# CrowPanel_ESP32_Display_1_28_R_Inch_V1_0.net
KiCad netlist of a schematic drawn in EAGLE
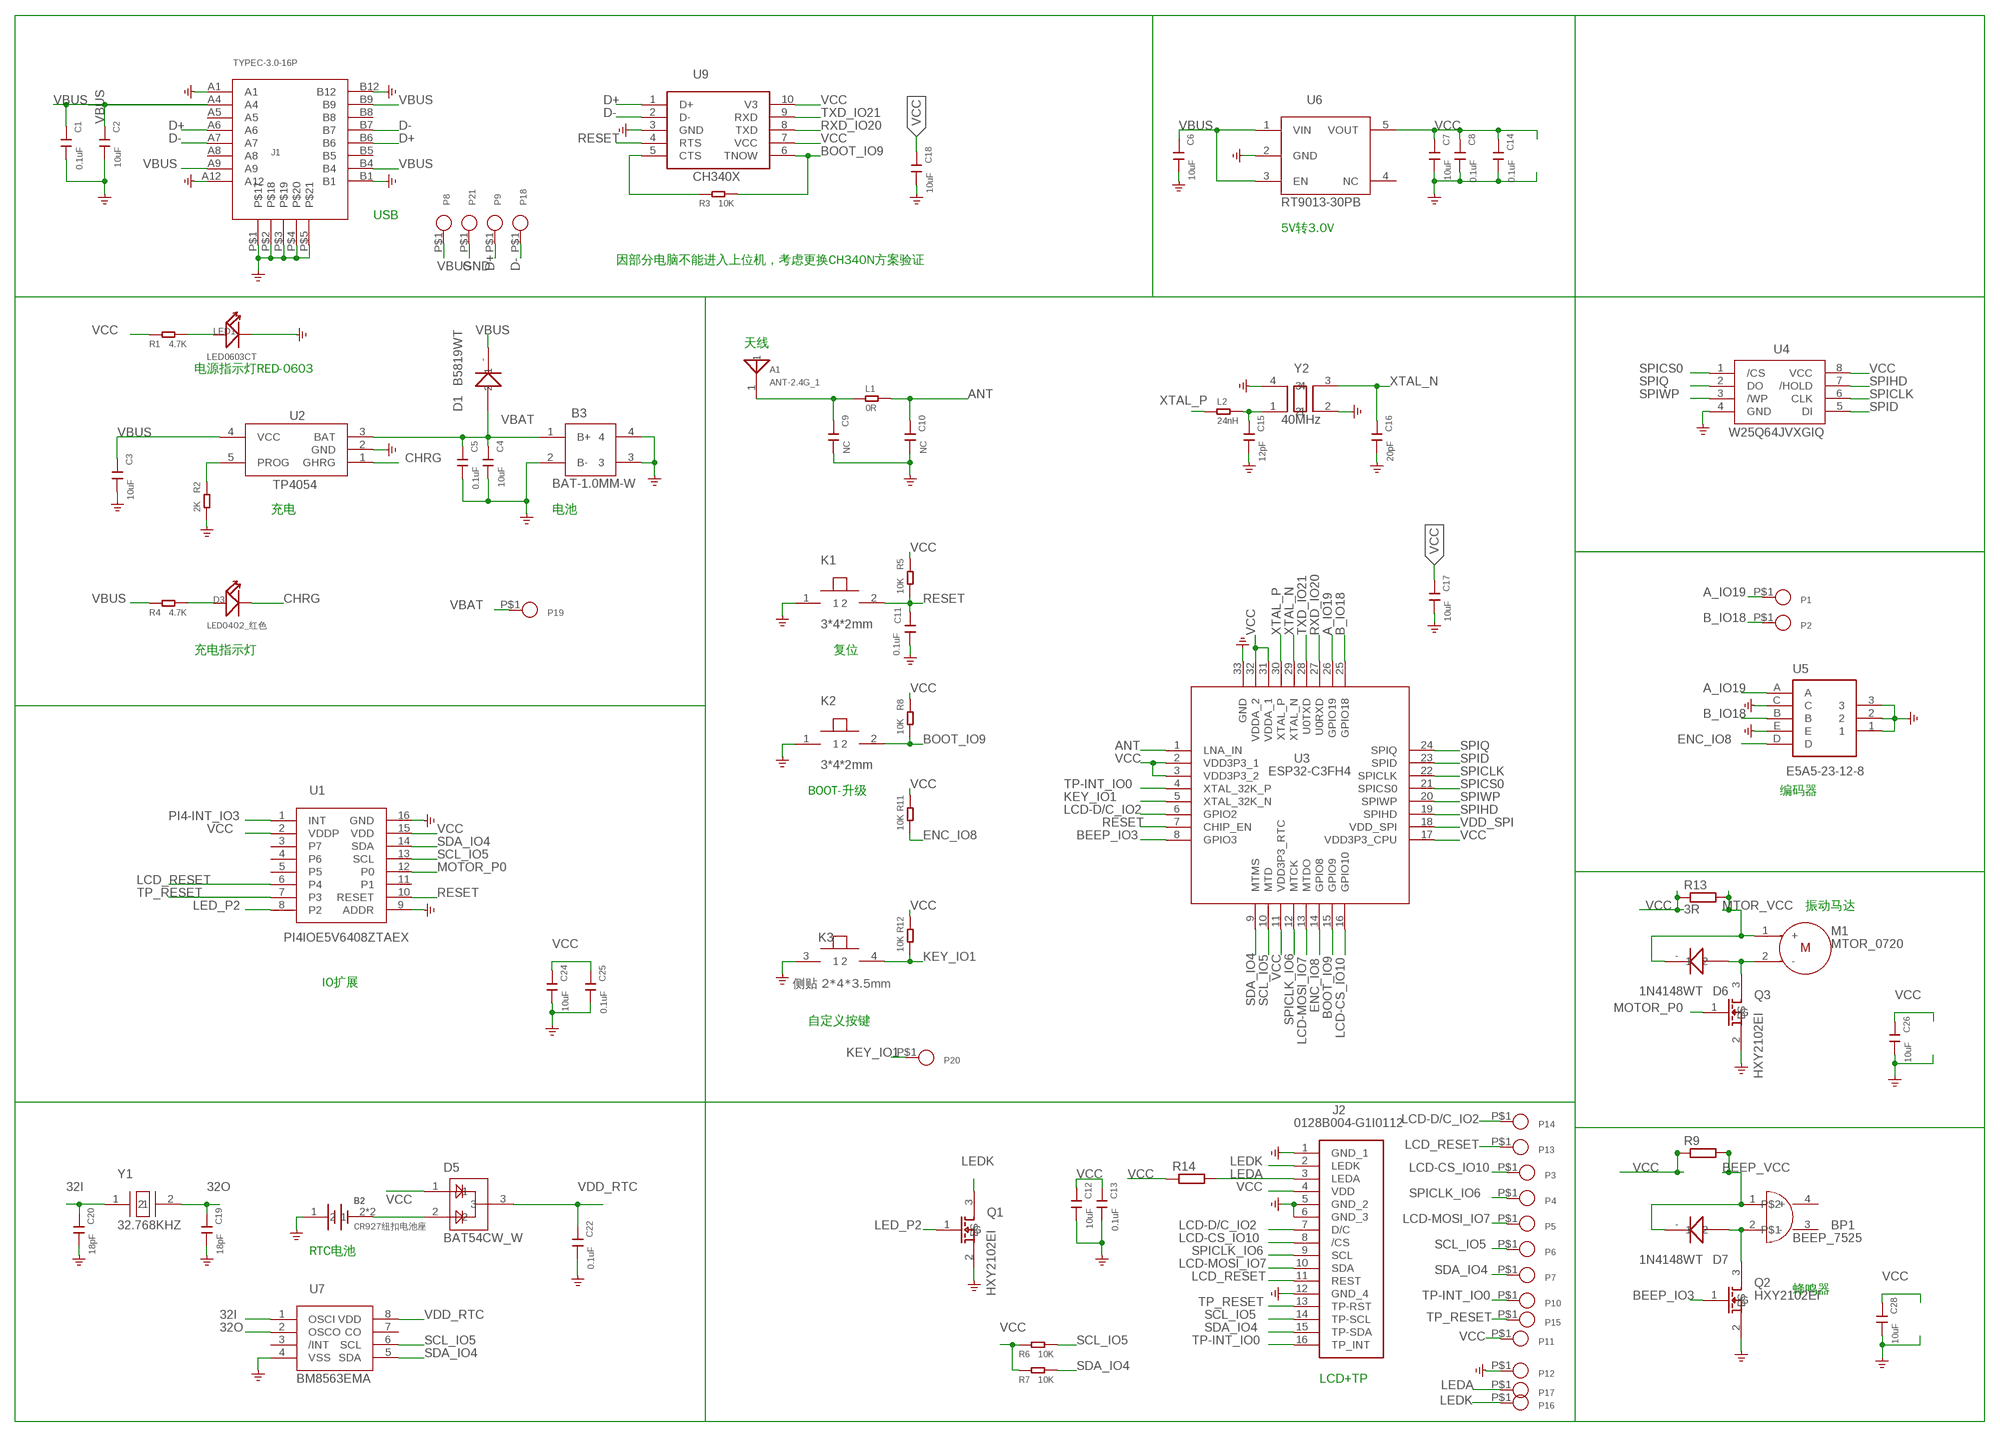
[diagram p0: schematic, sheet 1]

(export (version "E")
  (design (tool "Eeschema 10.0.6"))
  (components
    (comp (ref "A1")
      (value "ANT-2.4G_1")
      (footprint "eagle-import:ANT-2.4G_1")
      (libsource (lib "eagle-import") (part "ANT-2.4G_1"))
    )
    (comp (ref "B2")
      (value "CR927纽扣电池座")
      (footprint "eagle-import:POWER-BAT")
      (libsource (lib "eagle-import") (part "POWER-BAT"))
    )
    (comp (ref "B3")
      (value "BAT-1.0MM-W")
      (footprint "eagle-import:SH1.0MM-W")
      (libsource (lib "eagle-import") (part "BAT-1.0MM-W"))
    )
    (comp (ref "BP1")
      (value "BEEP_7525")
      (footprint "eagle-import:BEEP_7525")
      (libsource (lib "eagle-import") (part "BEEP_7525"))
    )
    (comp (ref "C1")
      (value "0.1uF")
      (footprint "eagle-import:0201_W")
      (libsource (lib "eagle-import") (part "C0402"))
    )
    (comp (ref "C2")
      (value "10uF")
      (footprint "eagle-import:0402")
      (libsource (lib "eagle-import") (part "C0402_W"))
    )
    (comp (ref "C3")
      (value "10uF")
      (footprint "eagle-import:0402")
      (libsource (lib "eagle-import") (part "C0402_W"))
    )
    (comp (ref "C4")
      (value "10uF")
      (footprint "eagle-import:0402")
      (libsource (lib "eagle-import") (part "C0402_W"))
    )
    (comp (ref "C5")
      (value "0.1uF")
      (footprint "eagle-import:0201_W")
      (libsource (lib "eagle-import") (part "C0402"))
    )
    (comp (ref "C6")
      (value "10uF")
      (footprint "eagle-import:0402")
      (libsource (lib "eagle-import") (part "C0402_W"))
    )
    (comp (ref "C7")
      (value "10uF")
      (footprint "eagle-import:0402")
      (libsource (lib "eagle-import") (part "C0402_W"))
    )
    (comp (ref "C8")
      (value "0.1uF")
      (footprint "eagle-import:0201_W")
      (libsource (lib "eagle-import") (part "C0402"))
    )
    (comp (ref "C9")
      (value "NC")
      (footprint "eagle-import:0201_W")
      (libsource (lib "eagle-import") (part "C0402"))
    )
    (comp (ref "C10")
      (value "NC")
      (footprint "eagle-import:0201_W")
      (libsource (lib "eagle-import") (part "C0402"))
    )
    (comp (ref "C11")
      (value "0.1uF")
      (footprint "eagle-import:0201_W")
      (libsource (lib "eagle-import") (part "C0402"))
    )
    (comp (ref "C12")
      (value "10uF")
      (footprint "eagle-import:0402")
      (libsource (lib "eagle-import") (part "C0402_W"))
    )
    (comp (ref "C13")
      (value "0.1uF")
      (footprint "eagle-import:0201_W")
      (libsource (lib "eagle-import") (part "C0402"))
    )
    (comp (ref "C14")
      (value "0.1uF")
      (footprint "eagle-import:0201_W")
      (libsource (lib "eagle-import") (part "C0402"))
    )
    (comp (ref "C15")
      (value "12pF")
      (footprint "eagle-import:0201_W")
      (libsource (lib "eagle-import") (part "C0402"))
    )
    (comp (ref "C16")
      (value "20pF")
      (footprint "eagle-import:0201_W")
      (libsource (lib "eagle-import") (part "C0402"))
    )
    (comp (ref "C17")
      (value "10uF")
      (footprint "eagle-import:0402")
      (libsource (lib "eagle-import") (part "C0402_W"))
    )
    (comp (ref "C18")
      (value "10uF")
      (footprint "eagle-import:0402")
      (libsource (lib "eagle-import") (part "C0402_W"))
    )
    (comp (ref "C19")
      (value "18pF")
      (footprint "eagle-import:0201_W")
      (libsource (lib "eagle-import") (part "C0402"))
    )
    (comp (ref "C20")
      (value "18pF")
      (footprint "eagle-import:0201_W")
      (libsource (lib "eagle-import") (part "C0402"))
    )
    (comp (ref "C22")
      (value "0.1uF")
      (footprint "eagle-import:0201_W")
      (libsource (lib "eagle-import") (part "C0402"))
    )
    (comp (ref "C24")
      (value "10uF")
      (footprint "eagle-import:0402")
      (libsource (lib "eagle-import") (part "C0402_W"))
    )
    (comp (ref "C25")
      (value "0.1uF")
      (footprint "eagle-import:0201_W")
      (libsource (lib "eagle-import") (part "C0402"))
    )
    (comp (ref "C26")
      (value "10uF")
      (footprint "eagle-import:0402")
      (libsource (lib "eagle-import") (part "C0402_W"))
    )
    (comp (ref "C28")
      (value "10uF")
      (footprint "eagle-import:0402")
      (libsource (lib "eagle-import") (part "C0402_W"))
    )
    (comp (ref "D1")
      (value "B5819WT")
      (footprint "eagle-import:SOD-523")
      (libsource (lib "eagle-import") (part "DIODE_W"))
    )
    (comp (ref "D3")
      (value "LED0402_红色")
      (footprint "eagle-import:LED-0402_W")
      (libsource (lib "eagle-import") (part "LED0402_W"))
    )
    (comp (ref "D5")
      (value "BAT54CW_W")
      (footprint "eagle-import:SOT-323_W")
      (libsource (lib "eagle-import") (part "BAT54CW_W"))
    )
    (comp (ref "D6")
      (value "1N4148WT")
      (footprint "eagle-import:SOD-523")
      (libsource (lib "eagle-import") (part "DIODE_W"))
    )
    (comp (ref "D7")
      (value "1N4148WT")
      (footprint "eagle-import:SOD-523")
      (libsource (lib "eagle-import") (part "DIODE_W"))
    )
    (comp (ref "J1")
      (value "TYPEC-3.0-16P")
      (footprint "eagle-import:KEVIN_3.0TYPEC-SMD")
      (libsource (lib "eagle-import") (part "KEVIN_TYPEC-3.0-16P-SMD"))
    )
    (comp (ref "J2")
      (value "0128B004-G1I0112")
      (footprint "eagle-import:16PIN-SMD")
      (libsource (lib "eagle-import") (part "0128B004-G1I0112"))
    )
    (comp (ref "K1")
      (value "3*4*2mm")
      (footprint "eagle-import:KEY-3X4_W")
      (libsource (lib "eagle-import") (part "KEY_3X4_W"))
    )
    (comp (ref "K2")
      (value "3*4*2mm")
      (footprint "eagle-import:KEY-3X4_W")
      (libsource (lib "eagle-import") (part "KEY_3X4_W"))
    )
    (comp (ref "K3")
      (value "侧贴 2*4*3.5mm")
      (footprint "eagle-import:KEY-3.5X4.5_C")
      (libsource (lib "eagle-import") (part "KEY_2X4X3.5_W"))
    )
    (comp (ref "L1")
      (value "0R")
      (footprint "eagle-import:0201_W")
      (libsource (lib "eagle-import") (part "R0402"))
    )
    (comp (ref "L2")
      (value "24nH")
      (footprint "eagle-import:0201_W")
      (libsource (lib "eagle-import") (part "R0402"))
    )
    (comp (ref "LED1")
      (value "LED0603CT")
      (footprint "eagle-import:LED-0603-CE")
      (libsource (lib "eagle-import") (part "LED0603CT"))
    )
    (comp (ref "M1")
      (value "MTOR_0720")
      (footprint "eagle-import:MOTOR-1")
      (libsource (lib "eagle-import") (part "MTOR_0720"))
    )
    (comp (ref "P1")
      (value "PADPAD-1.0MM")
      (footprint "eagle-import:PAD-1.0MM")
      (libsource (lib "eagle-import") (part "PADPAD-1.0MM"))
    )
    (comp (ref "P2")
      (value "PADPAD-1.0MM")
      (footprint "eagle-import:PAD-1.0MM")
      (libsource (lib "eagle-import") (part "PADPAD-1.0MM"))
    )
    (comp (ref "P3")
      (value "PADPAD-1.0MM")
      (footprint "eagle-import:PAD-1.0MM")
      (libsource (lib "eagle-import") (part "PADPAD-1.0MM"))
    )
    (comp (ref "P4")
      (value "PADPAD-1.0MM")
      (footprint "eagle-import:PAD-1.0MM")
      (libsource (lib "eagle-import") (part "PADPAD-1.0MM"))
    )
    (comp (ref "P5")
      (value "PADPAD-1.0MM")
      (footprint "eagle-import:PAD-1.0MM")
      (libsource (lib "eagle-import") (part "PADPAD-1.0MM"))
    )
    (comp (ref "P6")
      (value "PADPAD-1.0MM")
      (footprint "eagle-import:PAD-1.0MM")
      (libsource (lib "eagle-import") (part "PADPAD-1.0MM"))
    )
    (comp (ref "P7")
      (value "PADPAD-1.0MM")
      (footprint "eagle-import:PAD-1.0MM")
      (libsource (lib "eagle-import") (part "PADPAD-1.0MM"))
    )
    (comp (ref "P8")
      (value "PADPAD-1.0MM")
      (footprint "eagle-import:PAD-1.0MM")
      (libsource (lib "eagle-import") (part "PADPAD-1.0MM"))
    )
    (comp (ref "P9")
      (value "PADPAD-1.0MM")
      (footprint "eagle-import:PAD-1.0MM")
      (libsource (lib "eagle-import") (part "PADPAD-1.0MM"))
    )
    (comp (ref "P10")
      (value "PADPAD-1.0MM")
      (footprint "eagle-import:PAD-1.0MM")
      (libsource (lib "eagle-import") (part "PADPAD-1.0MM"))
    )
    (comp (ref "P11")
      (value "PADPAD-1.0MM")
      (footprint "eagle-import:PAD-1.0MM")
      (libsource (lib "eagle-import") (part "PADPAD-1.0MM"))
    )
    (comp (ref "P12")
      (value "PADPAD-1.0MM")
      (footprint "eagle-import:PAD-1.0MM")
      (libsource (lib "eagle-import") (part "PADPAD-1.0MM"))
    )
    (comp (ref "P13")
      (value "PADPAD-1.0MM")
      (footprint "eagle-import:PAD-1.0MM")
      (libsource (lib "eagle-import") (part "PADPAD-1.0MM"))
    )
    (comp (ref "P14")
      (value "PADPAD-1.0MM")
      (footprint "eagle-import:PAD-1.0MM")
      (libsource (lib "eagle-import") (part "PADPAD-1.0MM"))
    )
    (comp (ref "P15")
      (value "PADPAD-1.0MM")
      (footprint "eagle-import:PAD-1.0MM")
      (libsource (lib "eagle-import") (part "PADPAD-1.0MM"))
    )
    (comp (ref "P16")
      (value "PADPAD-1.0MM")
      (footprint "eagle-import:PAD-1.0MM")
      (libsource (lib "eagle-import") (part "PADPAD-1.0MM"))
    )
    (comp (ref "P17")
      (value "PADPAD-1.0MM")
      (footprint "eagle-import:PAD-1.0MM")
      (libsource (lib "eagle-import") (part "PADPAD-1.0MM"))
    )
    (comp (ref "P18")
      (value "PADPAD-1.0MM")
      (footprint "eagle-import:PAD-1.0MM")
      (libsource (lib "eagle-import") (part "PADPAD-1.0MM"))
    )
    (comp (ref "P19")
      (value "PADPAD-1.0MM")
      (footprint "eagle-import:PAD-1.0MM")
      (libsource (lib "eagle-import") (part "PADPAD-1.0MM"))
    )
    (comp (ref "P20")
      (value "PADPAD-1.0MM")
      (footprint "eagle-import:PAD-1.0MM")
      (libsource (lib "eagle-import") (part "PADPAD-1.0MM"))
    )
    (comp (ref "P21")
      (value "PADPAD-1.0MM")
      (footprint "eagle-import:PAD-1.0MM")
      (libsource (lib "eagle-import") (part "PADPAD-1.0MM"))
    )
    (comp (ref "Q1")
      (value "HXY2102EI")
      (footprint "eagle-import:SOT-323_W")
      (libsource (lib "eagle-import") (part "HXY2102EI"))
    )
    (comp (ref "Q2")
      (value "HXY2102EI")
      (footprint "eagle-import:SOT-323_W")
      (libsource (lib "eagle-import") (part "HXY2102EI"))
    )
    (comp (ref "Q3")
      (value "HXY2102EI")
      (footprint "eagle-import:SOT-323_W")
      (libsource (lib "eagle-import") (part "HXY2102EI"))
    )
    (comp (ref "R1")
      (value "4.7K")
      (footprint "eagle-import:0201_W")
      (libsource (lib "eagle-import") (part "R0402"))
    )
    (comp (ref "R2")
      (value "2K")
      (footprint "eagle-import:0201_W")
      (libsource (lib "eagle-import") (part "R0402"))
    )
    (comp (ref "R3")
      (value "10K")
      (footprint "eagle-import:0201_W")
      (libsource (lib "eagle-import") (part "R0402"))
    )
    (comp (ref "R4")
      (value "4.7K")
      (footprint "eagle-import:0201_W")
      (libsource (lib "eagle-import") (part "R0402"))
    )
    (comp (ref "R5")
      (value "10K")
      (footprint "eagle-import:0201_W")
      (libsource (lib "eagle-import") (part "R0402"))
    )
    (comp (ref "R6")
      (value "10K")
      (footprint "eagle-import:0201_W")
      (libsource (lib "eagle-import") (part "R0402"))
    )
    (comp (ref "R7")
      (value "10K")
      (footprint "eagle-import:0201_W")
      (libsource (lib "eagle-import") (part "R0402"))
    )
    (comp (ref "R8")
      (value "10K")
      (footprint "eagle-import:0201_W")
      (libsource (lib "eagle-import") (part "R0402"))
    )
    (comp (ref "R9")
      (value "R-EU_R0402")
      (footprint "eagle-import:R0402")
      (libsource (lib "eagle-import") (part "R-EU_R0402"))
    )
    (comp (ref "R11")
      (value "10K")
      (footprint "eagle-import:0201_W")
      (libsource (lib "eagle-import") (part "R0402"))
    )
    (comp (ref "R12")
      (value "10K")
      (footprint "eagle-import:0201_W")
      (libsource (lib "eagle-import") (part "R0402"))
    )
    (comp (ref "R13")
      (value "3R")
      (footprint "eagle-import:R0402")
      (libsource (lib "eagle-import") (part "R-EU_R0402"))
    )
    (comp (ref "R14")
      (value "R-EU_R0402")
      (footprint "eagle-import:R0402")
      (libsource (lib "eagle-import") (part "R-EU_R0402"))
    )
    (comp (ref "U1")
      (value "PI4IOE5V6408ZTAEX")
      (footprint "eagle-import:UQFN-16")
      (libsource (lib "eagle-import") (part "PI4IOE5V6408ZTAEX"))
    )
    (comp (ref "U2")
      (value "TP4054")
      (footprint "eagle-import:SOP23-5")
      (libsource (lib "eagle-import") (part "4054A"))
    )
    (comp (ref "U3")
      (value "ESP32-C3FH4")
      (footprint "eagle-import:QFN-32_W")
      (libsource (lib "eagle-import") (part "ESP32-C3"))
    )
    (comp (ref "U4")
      (value "W25Q64JVXGIQ")
      (footprint "eagle-import:XSON4X4")
      (libsource (lib "eagle-import") (part "W25Q64JVXGIQ"))
    )
    (comp (ref "U5")
      (value "E5A5-23-12-8")
      (footprint "eagle-import:E5A5-23-12-8")
      (fields (field (name "SPICEPREFIX") "X"))
      (libsource (lib "eagle-import") (part "E5A5-23-12-8"))
    )
    (comp (ref "U6")
      (value "RT9013-30PB")
      (footprint "eagle-import:SOT23-5_W")
      (libsource (lib "eagle-import") (part "RT9013"))
    )
    (comp (ref "U7")
      (value "BM8563EMA")
      (footprint "eagle-import:MSOP-8_W")
      (libsource (lib "eagle-import") (part "BM8563EMA"))
    )
    (comp (ref "U9")
      (value "CH340X")
      (footprint "eagle-import:MSOP-10_W")
      (libsource (lib "eagle-import") (part "CH340E"))
    )
    (comp (ref "Y1")
      (value "32.768KHZ")
      (footprint "eagle-import:3215_W")
      (libsource (lib "eagle-import") (part "32.768KHZ"))
    )
    (comp (ref "Y2")
      (value "40MHz")
      (footprint "eagle-import:3225_W")
      (libsource (lib "eagle-import") (part "3225_W"))
    )
  )
  (nets
    (net (code "1") (name "/32I") (class "Default")
      (node (ref "C20") (pin "1") (pinfunction "1_1") (pintype "passive"))
      (node (ref "U7") (pin "1") (pinfunction "OSCI_1") (pintype "bidirectional"))
      (node (ref "Y1") (pin "1") (pinfunction "1_1") (pintype "bidirectional"))
    )
    (net (code "2") (name "/32O") (class "Default")
      (node (ref "C19") (pin "1") (pinfunction "1_1") (pintype "passive"))
      (node (ref "U7") (pin "2") (pinfunction "OSCO_2") (pintype "bidirectional"))
      (node (ref "Y1") (pin "2") (pinfunction "2_2") (pintype "bidirectional"))
    )
    (net (code "3") (name "/ANT") (class "Default")
      (node (ref "C10") (pin "1") (pinfunction "1_1") (pintype "passive"))
      (node (ref "L1") (pin "2") (pinfunction "2_2") (pintype "passive"))
      (node (ref "U3") (pin "1") (pinfunction "LNA_IN_1") (pintype "bidirectional"))
    )
    (net (code "4") (name "/A_IO19") (class "Default")
      (node (ref "P1") (pin "P$1") (pinfunction "P$1_P$1") (pintype "bidirectional"))
      (node (ref "U3") (pin "26") (pinfunction "GPIO19_26") (pintype "bidirectional"))
      (node (ref "U5") (pin "A") (pinfunction "A_A") (pintype "bidirectional"))
    )
    (net (code "5") (name "/BEEP_IO3") (class "Default")
      (node (ref "Q2") (pin "1") (pinfunction "G_1") (pintype "bidirectional"))
      (node (ref "U3") (pin "8") (pinfunction "GPIO3_8") (pintype "bidirectional"))
    )
    (net (code "6") (name "/BEEP_VCC") (class "Default")
      (node (ref "BP1") (pin "1") (pinfunction "+_1") (pintype "bidirectional"))
      (node (ref "D7") (pin "-") (pinfunction "2_-") (pintype "bidirectional"))
      (node (ref "R9") (pin "2") (pinfunction "2_2") (pintype "passive"))
    )
    (net (code "7") (name "/BOOT_IO9") (class "Default")
      (node (ref "K2") (pin "2") (pinfunction "2_2") (pintype "bidirectional"))
      (node (ref "R3") (pin "2") (pinfunction "2_2") (pintype "passive"))
      (node (ref "R8") (pin "2") (pinfunction "2_2") (pintype "passive"))
      (node (ref "U3") (pin "15") (pinfunction "GPIO9_15") (pintype "bidirectional"))
      (node (ref "U9") (pin "6") (pinfunction "TNOW_6") (pintype "bidirectional"))
    )
    (net (code "8") (name "/B_IO18") (class "Default")
      (node (ref "P2") (pin "P$1") (pinfunction "P$1_P$1") (pintype "bidirectional"))
      (node (ref "U3") (pin "25") (pinfunction "GPIO18_25") (pintype "bidirectional"))
      (node (ref "U5") (pin "B") (pinfunction "B_B") (pintype "bidirectional"))
    )
    (net (code "9") (name "/CHRG") (class "Default")
      (node (ref "D3") (pin "2") (pinfunction "-_2") (pintype "passive"))
      (node (ref "U2") (pin "1") (pinfunction "GHRG_1") (pintype "bidirectional"))
    )
    (net (code "10") (name "/D+") (class "Default")
      (node (ref "J1") (pin "A6") (pinfunction "A6_A6") (pintype "bidirectional"))
      (node (ref "J1") (pin "B6") (pinfunction "B6_B6") (pintype "bidirectional"))
      (node (ref "P9") (pin "P$1") (pinfunction "P$1_P$1") (pintype "bidirectional"))
      (node (ref "U9") (pin "1") (pinfunction "D+_1") (pintype "bidirectional"))
    )
    (net (code "11") (name "/D-") (class "Default")
      (node (ref "J1") (pin "A7") (pinfunction "A7_A7") (pintype "bidirectional"))
      (node (ref "J1") (pin "B7") (pinfunction "B7_B7") (pintype "bidirectional"))
      (node (ref "P18") (pin "P$1") (pinfunction "P$1_P$1") (pintype "bidirectional"))
      (node (ref "U9") (pin "2") (pinfunction "D-_2") (pintype "bidirectional"))
    )
    (net (code "12") (name "/ENC_IO8") (class "Default")
      (node (ref "R11") (pin "2") (pinfunction "2_2") (pintype "passive"))
      (node (ref "U3") (pin "14") (pinfunction "GPIO8_14") (pintype "bidirectional"))
      (node (ref "U5") (pin "D") (pinfunction "D_D") (pintype "bidirectional"))
    )
    (net (code "13") (name "/KEY_IO1") (class "Default")
      (node (ref "K3") (pin "4") (pinfunction "2_4") (pintype "bidirectional"))
      (node (ref "P20") (pin "P$1") (pinfunction "P$1_P$1") (pintype "bidirectional"))
      (node (ref "R12") (pin "2") (pinfunction "2_2") (pintype "passive"))
      (node (ref "U3") (pin "5") (pinfunction "XTAL_32K_N_5") (pintype "bidirectional"))
    )
    (net (code "14") (name "/LCD-CS_IO10") (class "Default")
      (node (ref "J2") (pin "8") (pinfunction "/CS_8") (pintype "bidirectional"))
      (node (ref "P3") (pin "P$1") (pinfunction "P$1_P$1") (pintype "bidirectional"))
      (node (ref "U3") (pin "16") (pinfunction "GPIO10_16") (pintype "bidirectional"))
    )
    (net (code "15") (name "/LCD-D{slash}C_IO2") (class "Default")
      (node (ref "J2") (pin "7") (pinfunction "D/C_7") (pintype "bidirectional"))
      (node (ref "P14") (pin "P$1") (pinfunction "P$1_P$1") (pintype "bidirectional"))
      (node (ref "U3") (pin "6") (pinfunction "GPIO2_6") (pintype "bidirectional"))
    )
    (net (code "16") (name "/LCD-MOSI_IO7") (class "Default")
      (node (ref "J2") (pin "10") (pinfunction "SDA_10") (pintype "bidirectional"))
      (node (ref "P5") (pin "P$1") (pinfunction "P$1_P$1") (pintype "bidirectional"))
      (node (ref "U3") (pin "13") (pinfunction "MTDO_13") (pintype "bidirectional"))
    )
    (net (code "17") (name "/LCD_RESET") (class "Default")
      (node (ref "J2") (pin "11") (pinfunction "REST_11") (pintype "bidirectional"))
      (node (ref "P13") (pin "P$1") (pinfunction "P$1_P$1") (pintype "bidirectional"))
      (node (ref "U1") (pin "6") (pinfunction "P4_6") (pintype "bidirectional"))
    )
    (net (code "18") (name "/LEDA") (class "Default")
      (node (ref "J2") (pin "3") (pinfunction "LEDA_3") (pintype "bidirectional"))
      (node (ref "P17") (pin "P$1") (pinfunction "P$1_P$1") (pintype "bidirectional"))
      (node (ref "R14") (pin "2") (pinfunction "2_2") (pintype "passive"))
    )
    (net (code "19") (name "/LEDK") (class "Default")
      (node (ref "J2") (pin "2") (pinfunction "LEDK_2") (pintype "bidirectional"))
      (node (ref "P16") (pin "P$1") (pinfunction "P$1_P$1") (pintype "bidirectional"))
      (node (ref "Q1") (pin "3") (pinfunction "D_3") (pintype "bidirectional"))
    )
    (net (code "20") (name "/LED_P2") (class "Default")
      (node (ref "Q1") (pin "1") (pinfunction "G_1") (pintype "bidirectional"))
      (node (ref "U1") (pin "8") (pinfunction "P2_8") (pintype "bidirectional"))
    )
    (net (code "21") (name "/MOTOR_P0") (class "Default")
      (node (ref "Q3") (pin "1") (pinfunction "G_1") (pintype "bidirectional"))
      (node (ref "U1") (pin "12") (pinfunction "P0_12") (pintype "bidirectional"))
    )
    (net (code "22") (name "/MTOR_VCC") (class "Default")
      (node (ref "D6") (pin "-") (pinfunction "2_-") (pintype "bidirectional"))
      (node (ref "M1") (pin "1") (pinfunction "+_1") (pintype "bidirectional"))
      (node (ref "R13") (pin "2") (pinfunction "2_2") (pintype "passive"))
    )
    (net (code "23") (name "/PI4-INT_IO3") (class "Default")
      (node (ref "U1") (pin "1") (pinfunction "INT_1") (pintype "bidirectional"))
    )
    (net (code "24") (name "/RESET") (class "Default")
      (node (ref "C11") (pin "1") (pinfunction "1_1") (pintype "passive"))
      (node (ref "K1") (pin "2") (pinfunction "2_2") (pintype "bidirectional"))
      (node (ref "R5") (pin "2") (pinfunction "2_2") (pintype "passive"))
      (node (ref "U1") (pin "10") (pinfunction "RESET_10") (pintype "bidirectional"))
      (node (ref "U3") (pin "7") (pinfunction "CHIP_EN_7") (pintype "bidirectional"))
      (node (ref "U9") (pin "4") (pinfunction "RTS_4") (pintype "bidirectional"))
    )
    (net (code "25") (name "/RXD_IO20") (class "Default")
      (node (ref "U3") (pin "27") (pinfunction "U0RXD_27") (pintype "bidirectional"))
      (node (ref "U9") (pin "8") (pinfunction "TXD_8") (pintype "bidirectional"))
    )
    (net (code "26") (name "/SCL_IO5") (class "Default")
      (node (ref "J2") (pin "14") (pinfunction "TP-SCL_14") (pintype "bidirectional"))
      (node (ref "P6") (pin "P$1") (pinfunction "P$1_P$1") (pintype "bidirectional"))
      (node (ref "R6") (pin "2") (pinfunction "2_2") (pintype "passive"))
      (node (ref "U1") (pin "13") (pinfunction "SCL_13") (pintype "bidirectional"))
      (node (ref "U3") (pin "10") (pinfunction "MTD_10") (pintype "bidirectional"))
      (node (ref "U7") (pin "6") (pinfunction "SCL_6") (pintype "bidirectional"))
    )
    (net (code "27") (name "/SDA_IO4") (class "Default")
      (node (ref "J2") (pin "15") (pinfunction "TP-SDA_15") (pintype "bidirectional"))
      (node (ref "P7") (pin "P$1") (pinfunction "P$1_P$1") (pintype "bidirectional"))
      (node (ref "R7") (pin "2") (pinfunction "2_2") (pintype "passive"))
      (node (ref "U1") (pin "14") (pinfunction "SDA_14") (pintype "bidirectional"))
      (node (ref "U3") (pin "9") (pinfunction "MTMS_9") (pintype "bidirectional"))
      (node (ref "U7") (pin "5") (pinfunction "SDA_5") (pintype "bidirectional"))
    )
    (net (code "28") (name "/SPICLK") (class "Default")
      (node (ref "U3") (pin "22") (pinfunction "SPICLK_22") (pintype "bidirectional"))
      (node (ref "U4") (pin "6") (pinfunction "CLK_6") (pintype "bidirectional"))
    )
    (net (code "29") (name "/SPICLK_IO6") (class "Default")
      (node (ref "J2") (pin "9") (pinfunction "SCL_9") (pintype "bidirectional"))
      (node (ref "P4") (pin "P$1") (pinfunction "P$1_P$1") (pintype "bidirectional"))
      (node (ref "U3") (pin "12") (pinfunction "MTCK_12") (pintype "bidirectional"))
    )
    (net (code "30") (name "/SPICS0") (class "Default")
      (node (ref "U3") (pin "21") (pinfunction "SPICS0_21") (pintype "bidirectional"))
      (node (ref "U4") (pin "1") (pinfunction "/CS_1") (pintype "bidirectional"))
    )
    (net (code "31") (name "/SPID") (class "Default")
      (node (ref "U3") (pin "23") (pinfunction "SPID_23") (pintype "bidirectional"))
      (node (ref "U4") (pin "5") (pinfunction "DI_5") (pintype "bidirectional"))
    )
    (net (code "32") (name "/SPIHD") (class "Default")
      (node (ref "U3") (pin "19") (pinfunction "SPIHD_19") (pintype "bidirectional"))
      (node (ref "U4") (pin "7") (pinfunction "/HOLD_7") (pintype "bidirectional"))
    )
    (net (code "33") (name "/SPIQ") (class "Default")
      (node (ref "U3") (pin "24") (pinfunction "SPIQ_24") (pintype "bidirectional"))
      (node (ref "U4") (pin "2") (pinfunction "DO_2") (pintype "bidirectional"))
    )
    (net (code "34") (name "/SPIWP") (class "Default")
      (node (ref "U3") (pin "20") (pinfunction "SPIWP_20") (pintype "bidirectional"))
      (node (ref "U4") (pin "3") (pinfunction "/WP_3") (pintype "bidirectional"))
    )
    (net (code "35") (name "/TP-INT_IO0") (class "Default")
      (node (ref "J2") (pin "16") (pinfunction "TP_INT_16") (pintype "bidirectional"))
      (node (ref "P10") (pin "P$1") (pinfunction "P$1_P$1") (pintype "bidirectional"))
      (node (ref "U3") (pin "4") (pinfunction "XTAL_32K_P_4") (pintype "bidirectional"))
    )
    (net (code "36") (name "/TP_RESET") (class "Default")
      (node (ref "J2") (pin "13") (pinfunction "TP-RST_13") (pintype "bidirectional"))
      (node (ref "P15") (pin "P$1") (pinfunction "P$1_P$1") (pintype "bidirectional"))
      (node (ref "U1") (pin "7") (pinfunction "P3_7") (pintype "bidirectional"))
    )
    (net (code "37") (name "/TXD_IO21") (class "Default")
      (node (ref "U3") (pin "28") (pinfunction "U0TXD_28") (pintype "bidirectional"))
      (node (ref "U9") (pin "9") (pinfunction "RXD_9") (pintype "bidirectional"))
    )
    (net (code "38") (name "/VBAT") (class "Default")
      (node (ref "B3") (pin "1") (pinfunction "B+_1") (pintype "bidirectional"))
      (node (ref "C4") (pin "1") (pinfunction "1_1") (pintype "passive"))
      (node (ref "C5") (pin "1") (pinfunction "1_1") (pintype "passive"))
      (node (ref "D1") (pin "+") (pinfunction "1_+") (pintype "bidirectional"))
      (node (ref "P19") (pin "P$1") (pinfunction "P$1_P$1") (pintype "bidirectional"))
      (node (ref "U2") (pin "3") (pinfunction "BAT_3") (pintype "bidirectional"))
    )
    (net (code "39") (name "/VBUS") (class "Default")
      (node (ref "C1") (pin "1") (pinfunction "1_1") (pintype "passive"))
      (node (ref "C2") (pin "1") (pinfunction "1_1") (pintype "passive"))
      (node (ref "C3") (pin "1") (pinfunction "1_1") (pintype "passive"))
      (node (ref "C6") (pin "1") (pinfunction "1_1") (pintype "passive"))
      (node (ref "D1") (pin "-") (pinfunction "2_-") (pintype "bidirectional"))
      (node (ref "J1") (pin "A4") (pinfunction "A4_A4") (pintype "bidirectional"))
      (node (ref "J1") (pin "A9") (pinfunction "A9_A9") (pintype "bidirectional"))
      (node (ref "J1") (pin "B4") (pinfunction "B4_B4") (pintype "bidirectional"))
      (node (ref "J1") (pin "B9") (pinfunction "B9_B9") (pintype "bidirectional"))
      (node (ref "P8") (pin "P$1") (pinfunction "P$1_P$1") (pintype "bidirectional"))
      (node (ref "R4") (pin "1") (pinfunction "1_1") (pintype "passive"))
      (node (ref "U2") (pin "4") (pinfunction "VCC_4") (pintype "bidirectional"))
      (node (ref "U6") (pin "1") (pinfunction "VIN_1") (pintype "bidirectional"))
      (node (ref "U6") (pin "3") (pinfunction "EN_3") (pintype "bidirectional"))
    )
    (net (code "40") (name "/VDD_RTC") (class "Default")
      (node (ref "C22") (pin "1") (pinfunction "1_1") (pintype "passive"))
      (node (ref "D5") (pin "3") (pinfunction "3_3") (pintype "bidirectional"))
      (node (ref "U7") (pin "8") (pinfunction "VDD_8") (pintype "bidirectional"))
    )
    (net (code "41") (name "/VDD_SPI") (class "Default")
      (node (ref "U3") (pin "18") (pinfunction "VDD_SPI_18") (pintype "bidirectional"))
    )
    (net (code "42") (name "/XTAL_N") (class "Default")
      (node (ref "C16") (pin "1") (pinfunction "1_1") (pintype "passive"))
      (node (ref "U3") (pin "29") (pinfunction "XTAL_N_29") (pintype "bidirectional"))
      (node (ref "Y2") (pin "3") (pinfunction "3_3") (pintype "bidirectional"))
    )
    (net (code "43") (name "/XTAL_P") (class "Default")
      (node (ref "L2") (pin "1") (pinfunction "1_1") (pintype "passive"))
      (node (ref "U3") (pin "30") (pinfunction "XTAL_P_30") (pintype "bidirectional"))
    )
    (net (code "44") (name "GND_W") (class "Default")
      (node (ref "B2") (pin "1") (pinfunction "1_1") (pintype "bidirectional"))
      (node (ref "B3") (pin "2") (pinfunction "B-_2") (pintype "bidirectional"))
      (node (ref "B3") (pin "3") (pinfunction "3_3") (pintype "bidirectional"))
      (node (ref "B3") (pin "4") (pinfunction "4_4") (pintype "bidirectional"))
      (node (ref "C1") (pin "2") (pinfunction "2_2") (pintype "passive"))
      (node (ref "C10") (pin "2") (pinfunction "2_2") (pintype "passive"))
      (node (ref "C11") (pin "2") (pinfunction "2_2") (pintype "passive"))
      (node (ref "C12") (pin "2") (pinfunction "2_2") (pintype "passive"))
      (node (ref "C13") (pin "2") (pinfunction "2_2") (pintype "passive"))
      (node (ref "C14") (pin "2") (pinfunction "2_2") (pintype "passive"))
      (node (ref "C15") (pin "2") (pinfunction "2_2") (pintype "passive"))
      (node (ref "C16") (pin "2") (pinfunction "2_2") (pintype "passive"))
      (node (ref "C17") (pin "2") (pinfunction "2_2") (pintype "passive"))
      (node (ref "C18") (pin "2") (pinfunction "2_2") (pintype "passive"))
      (node (ref "C19") (pin "2") (pinfunction "2_2") (pintype "passive"))
      (node (ref "C2") (pin "2") (pinfunction "2_2") (pintype "passive"))
      (node (ref "C20") (pin "2") (pinfunction "2_2") (pintype "passive"))
      (node (ref "C22") (pin "2") (pinfunction "2_2") (pintype "passive"))
      (node (ref "C24") (pin "2") (pinfunction "2_2") (pintype "passive"))
      (node (ref "C25") (pin "2") (pinfunction "2_2") (pintype "passive"))
      (node (ref "C26") (pin "2") (pinfunction "2_2") (pintype "passive"))
      (node (ref "C28") (pin "2") (pinfunction "2_2") (pintype "passive"))
      (node (ref "C3") (pin "2") (pinfunction "2_2") (pintype "passive"))
      (node (ref "C4") (pin "2") (pinfunction "2_2") (pintype "passive"))
      (node (ref "C5") (pin "2") (pinfunction "2_2") (pintype "passive"))
      (node (ref "C6") (pin "2") (pinfunction "2_2") (pintype "passive"))
      (node (ref "C7") (pin "2") (pinfunction "2_2") (pintype "passive"))
      (node (ref "C8") (pin "2") (pinfunction "2_2") (pintype "passive"))
      (node (ref "C9") (pin "2") (pinfunction "2_2") (pintype "passive"))
      (node (ref "J1") (pin "A1") (pinfunction "A1_A1") (pintype "bidirectional"))
      (node (ref "J1") (pin "A12") (pinfunction "A12_A12") (pintype "bidirectional"))
      (node (ref "J1") (pin "B1") (pinfunction "B1_B1") (pintype "bidirectional"))
      (node (ref "J1") (pin "B12") (pinfunction "B12_B12") (pintype "bidirectional"))
      (node (ref "J1") (pin "P$1") (pinfunction "P$17_P$1") (pintype "bidirectional"))
      (node (ref "J1") (pin "P$2") (pinfunction "P$18_P$2") (pintype "bidirectional"))
      (node (ref "J1") (pin "P$3") (pinfunction "P$19_P$3") (pintype "bidirectional"))
      (node (ref "J1") (pin "P$4") (pinfunction "P$20_P$4") (pintype "bidirectional"))
      (node (ref "J1") (pin "P$5") (pinfunction "P$21_P$5") (pintype "bidirectional"))
      (node (ref "J2") (pin "1") (pinfunction "GND_1_1") (pintype "bidirectional"))
      (node (ref "J2") (pin "12") (pinfunction "GND_4_12") (pintype "bidirectional"))
      (node (ref "J2") (pin "5") (pinfunction "GND_2_5") (pintype "bidirectional"))
      (node (ref "J2") (pin "6") (pinfunction "GND_3_6") (pintype "bidirectional"))
      (node (ref "K1") (pin "1") (pinfunction "1_1") (pintype "bidirectional"))
      (node (ref "K2") (pin "1") (pinfunction "1_1") (pintype "bidirectional"))
      (node (ref "K3") (pin "3") (pinfunction "1_3") (pintype "bidirectional"))
      (node (ref "LED1") (pin "2") (pinfunction "-_2") (pintype "passive"))
      (node (ref "P12") (pin "P$1") (pinfunction "P$1_P$1") (pintype "bidirectional"))
      (node (ref "P21") (pin "P$1") (pinfunction "P$1_P$1") (pintype "bidirectional"))
      (node (ref "Q1") (pin "2") (pinfunction "S_2") (pintype "bidirectional"))
      (node (ref "Q2") (pin "2") (pinfunction "S_2") (pintype "bidirectional"))
      (node (ref "Q3") (pin "2") (pinfunction "S_2") (pintype "bidirectional"))
      (node (ref "R2") (pin "2") (pinfunction "2_2") (pintype "passive"))
      (node (ref "U1") (pin "16") (pinfunction "GND_16") (pintype "bidirectional"))
      (node (ref "U1") (pin "9") (pinfunction "ADDR_9") (pintype "bidirectional"))
      (node (ref "U2") (pin "2") (pinfunction "GND_2") (pintype "bidirectional"))
      (node (ref "U3") (pin "33") (pinfunction "GND_33") (pintype "bidirectional"))
      (node (ref "U4") (pin "4") (pinfunction "GND_4") (pintype "bidirectional"))
      (node (ref "U5") (pin "1") (pinfunction "1_1") (pintype "bidirectional"))
      (node (ref "U5") (pin "2") (pinfunction "2_2") (pintype "bidirectional"))
      (node (ref "U5") (pin "3") (pinfunction "3_3") (pintype "bidirectional"))
      (node (ref "U5") (pin "C") (pinfunction "C_C") (pintype "bidirectional"))
      (node (ref "U5") (pin "E") (pinfunction "E_E") (pintype "bidirectional"))
      (node (ref "U6") (pin "2") (pinfunction "GND_2") (pintype "bidirectional"))
      (node (ref "U7") (pin "4") (pinfunction "VSS_4") (pintype "bidirectional"))
      (node (ref "U9") (pin "3") (pinfunction "GND_3") (pintype "bidirectional"))
      (node (ref "Y2") (pin "2") (pinfunction "2_2") (pintype "bidirectional"))
      (node (ref "Y2") (pin "4") (pinfunction "4_4") (pintype "bidirectional"))
    )
    (net (code "45") (name "Net-(A1-Pad1)") (class "Default")
      (node (ref "A1") (pin "1") (pinfunction "1_1") (pintype "bidirectional"))
      (node (ref "C9") (pin "1") (pinfunction "1_1") (pintype "passive"))
      (node (ref "L1") (pin "1") (pinfunction "1_1") (pintype "passive"))
    )
    (net (code "46") (name "Net-(B2-2-Pad3)") (class "Default")
      (node (ref "B2") (pin "2") (pinfunction "2_2") (pintype "bidirectional"))
      (node (ref "B2") (pin "3") (pinfunction "2_3") (pintype "bidirectional"))
      (node (ref "D5") (pin "2") (pinfunction "2_2") (pintype "bidirectional"))
    )
    (net (code "47") (name "Net-(BP1--)") (class "Default")
      (node (ref "BP1") (pin "2") (pinfunction "-_2") (pintype "bidirectional"))
      (node (ref "D7") (pin "+") (pinfunction "1_+") (pintype "bidirectional"))
      (node (ref "Q2") (pin "3") (pinfunction "D_3") (pintype "bidirectional"))
    )
    (net (code "48") (name "Net-(C15-Pad1)") (class "Default")
      (node (ref "C15") (pin "1") (pinfunction "1_1") (pintype "passive"))
      (node (ref "L2") (pin "2") (pinfunction "2_2") (pintype "passive"))
      (node (ref "Y2") (pin "1") (pinfunction "1_1") (pintype "bidirectional"))
    )
    (net (code "49") (name "Net-(D3-+)") (class "Default")
      (node (ref "D3") (pin "1") (pinfunction "+_1") (pintype "passive"))
      (node (ref "R4") (pin "2") (pinfunction "2_2") (pintype "passive"))
    )
    (net (code "50") (name "Net-(D6-1)") (class "Default")
      (node (ref "D6") (pin "+") (pinfunction "1_+") (pintype "bidirectional"))
      (node (ref "M1") (pin "2") (pinfunction "-_2") (pintype "bidirectional"))
      (node (ref "Q3") (pin "3") (pinfunction "D_3") (pintype "bidirectional"))
    )
    (net (code "51") (name "Net-(LED1-+)") (class "Default")
      (node (ref "LED1") (pin "1") (pinfunction "+_1") (pintype "passive"))
      (node (ref "R1") (pin "2") (pinfunction "2_2") (pintype "passive"))
    )
    (net (code "52") (name "Net-(U2-PROG)") (class "Default")
      (node (ref "R2") (pin "1") (pinfunction "1_1") (pintype "passive"))
      (node (ref "U2") (pin "5") (pinfunction "PROG_5") (pintype "bidirectional"))
    )
    (net (code "53") (name "Net-(U9-CTS)") (class "Default")
      (node (ref "R3") (pin "1") (pinfunction "1_1") (pintype "passive"))
      (node (ref "U9") (pin "5") (pinfunction "CTS_5") (pintype "bidirectional"))
    )
    (net (code "54") (name "VCC") (class "Default")
      (node (ref "C12") (pin "1") (pinfunction "1_1") (pintype "passive"))
      (node (ref "C13") (pin "1") (pinfunction "1_1") (pintype "passive"))
      (node (ref "C14") (pin "1") (pinfunction "1_1") (pintype "passive"))
      (node (ref "C17") (pin "1") (pinfunction "1_1") (pintype "passive"))
      (node (ref "C18") (pin "1") (pinfunction "1_1") (pintype "passive"))
      (node (ref "C24") (pin "1") (pinfunction "1_1") (pintype "passive"))
      (node (ref "C25") (pin "1") (pinfunction "1_1") (pintype "passive"))
      (node (ref "C26") (pin "1") (pinfunction "1_1") (pintype "passive"))
      (node (ref "C28") (pin "1") (pinfunction "1_1") (pintype "passive"))
      (node (ref "C7") (pin "1") (pinfunction "1_1") (pintype "passive"))
      (node (ref "C8") (pin "1") (pinfunction "1_1") (pintype "passive"))
      (node (ref "D5") (pin "1") (pinfunction "1_1") (pintype "bidirectional"))
      (node (ref "J2") (pin "4") (pinfunction "VDD_4") (pintype "bidirectional"))
      (node (ref "P11") (pin "P$1") (pinfunction "P$1_P$1") (pintype "bidirectional"))
      (node (ref "R1") (pin "1") (pinfunction "1_1") (pintype "passive"))
      (node (ref "R11") (pin "1") (pinfunction "1_1") (pintype "passive"))
      (node (ref "R12") (pin "1") (pinfunction "1_1") (pintype "passive"))
      (node (ref "R13") (pin "1") (pinfunction "1_1") (pintype "passive"))
      (node (ref "R14") (pin "1") (pinfunction "1_1") (pintype "passive"))
      (node (ref "R5") (pin "1") (pinfunction "1_1") (pintype "passive"))
      (node (ref "R6") (pin "1") (pinfunction "1_1") (pintype "passive"))
      (node (ref "R7") (pin "1") (pinfunction "1_1") (pintype "passive"))
      (node (ref "R8") (pin "1") (pinfunction "1_1") (pintype "passive"))
      (node (ref "R9") (pin "1") (pinfunction "1_1") (pintype "passive"))
      (node (ref "U1") (pin "15") (pinfunction "VDD_15") (pintype "bidirectional"))
      (node (ref "U1") (pin "2") (pinfunction "VDDP_2") (pintype "bidirectional"))
      (node (ref "U3") (pin "11") (pinfunction "VDD3P3_RTC_11") (pintype "bidirectional"))
      (node (ref "U3") (pin "17") (pinfunction "VDD3P3_CPU_17") (pintype "bidirectional"))
      (node (ref "U3") (pin "2") (pinfunction "VDD3P3_1_2") (pintype "bidirectional"))
      (node (ref "U3") (pin "3") (pinfunction "VDD3P3_2_3") (pintype "bidirectional"))
      (node (ref "U3") (pin "31") (pinfunction "VDDA_1_31") (pintype "bidirectional"))
      (node (ref "U3") (pin "32") (pinfunction "VDDA_2_32") (pintype "bidirectional"))
      (node (ref "U4") (pin "8") (pinfunction "VCC_8") (pintype "bidirectional"))
      (node (ref "U6") (pin "5") (pinfunction "VOUT_5") (pintype "bidirectional"))
      (node (ref "U9") (pin "10") (pinfunction "V3_10") (pintype "bidirectional"))
      (node (ref "U9") (pin "7") (pinfunction "VCC_7") (pintype "bidirectional"))
    )
    (net (code "55") (name "unconnected-(BP1-P$1-Pad3)") (class "Default")
      (node (ref "BP1") (pin "3") (pinfunction "P$1_3") (pintype "bidirectional"))
    )
    (net (code "56") (name "unconnected-(BP1-P$2-Pad4)") (class "Default")
      (node (ref "BP1") (pin "4") (pinfunction "P$2_4") (pintype "bidirectional"))
    )
    (net (code "57") (name "unconnected-(J1-PadA5)") (class "Default")
      (node (ref "J1") (pin "A5") (pinfunction "A5_A5") (pintype "bidirectional"))
    )
    (net (code "58") (name "unconnected-(J1-PadA8)") (class "Default")
      (node (ref "J1") (pin "A8") (pinfunction "A8_A8") (pintype "bidirectional"))
    )
    (net (code "59") (name "unconnected-(J1-PadB5)") (class "Default")
      (node (ref "J1") (pin "B5") (pinfunction "B5_B5") (pintype "bidirectional"))
    )
    (net (code "60") (name "unconnected-(J1-PadB8)") (class "Default")
      (node (ref "J1") (pin "B8") (pinfunction "B8_B8") (pintype "bidirectional"))
    )
    (net (code "61") (name "unconnected-(U1-P1-Pad11)") (class "Default")
      (node (ref "U1") (pin "11") (pinfunction "P1_11") (pintype "bidirectional"))
    )
    (net (code "62") (name "unconnected-(U1-P5-Pad5)") (class "Default")
      (node (ref "U1") (pin "5") (pinfunction "P5_5") (pintype "bidirectional"))
    )
    (net (code "63") (name "unconnected-(U1-P6-Pad4)") (class "Default")
      (node (ref "U1") (pin "4") (pinfunction "P6_4") (pintype "bidirectional"))
    )
    (net (code "64") (name "unconnected-(U1-P7-Pad3)") (class "Default")
      (node (ref "U1") (pin "3") (pinfunction "P7_3") (pintype "bidirectional"))
    )
    (net (code "65") (name "unconnected-(U6-NC-Pad4)") (class "Default")
      (node (ref "U6") (pin "4") (pinfunction "NC_4") (pintype "bidirectional"))
    )
    (net (code "66") (name "unconnected-(U7-CO-Pad7)") (class "Default")
      (node (ref "U7") (pin "7") (pinfunction "CO_7") (pintype "bidirectional"))
    )
    (net (code "67") (name "unconnected-(U7-{slash}INT-Pad3)") (class "Default")
      (node (ref "U7") (pin "3") (pinfunction "/INT_3") (pintype "bidirectional"))
    )
  )
)
